# 03-POWER.net
KiCad netlist of a schematic drawn in Altium Designer
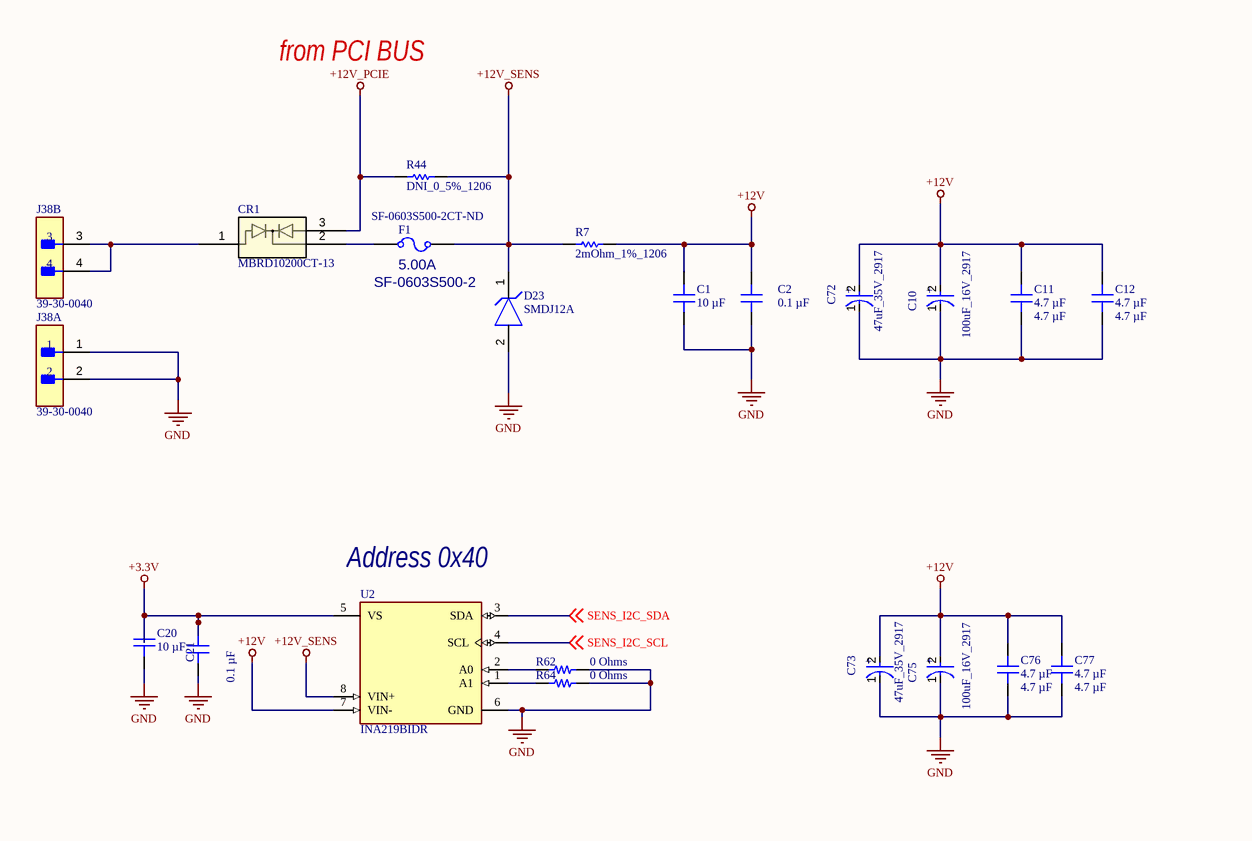
[diagram p0: 03-POWER.SchDoc, left]
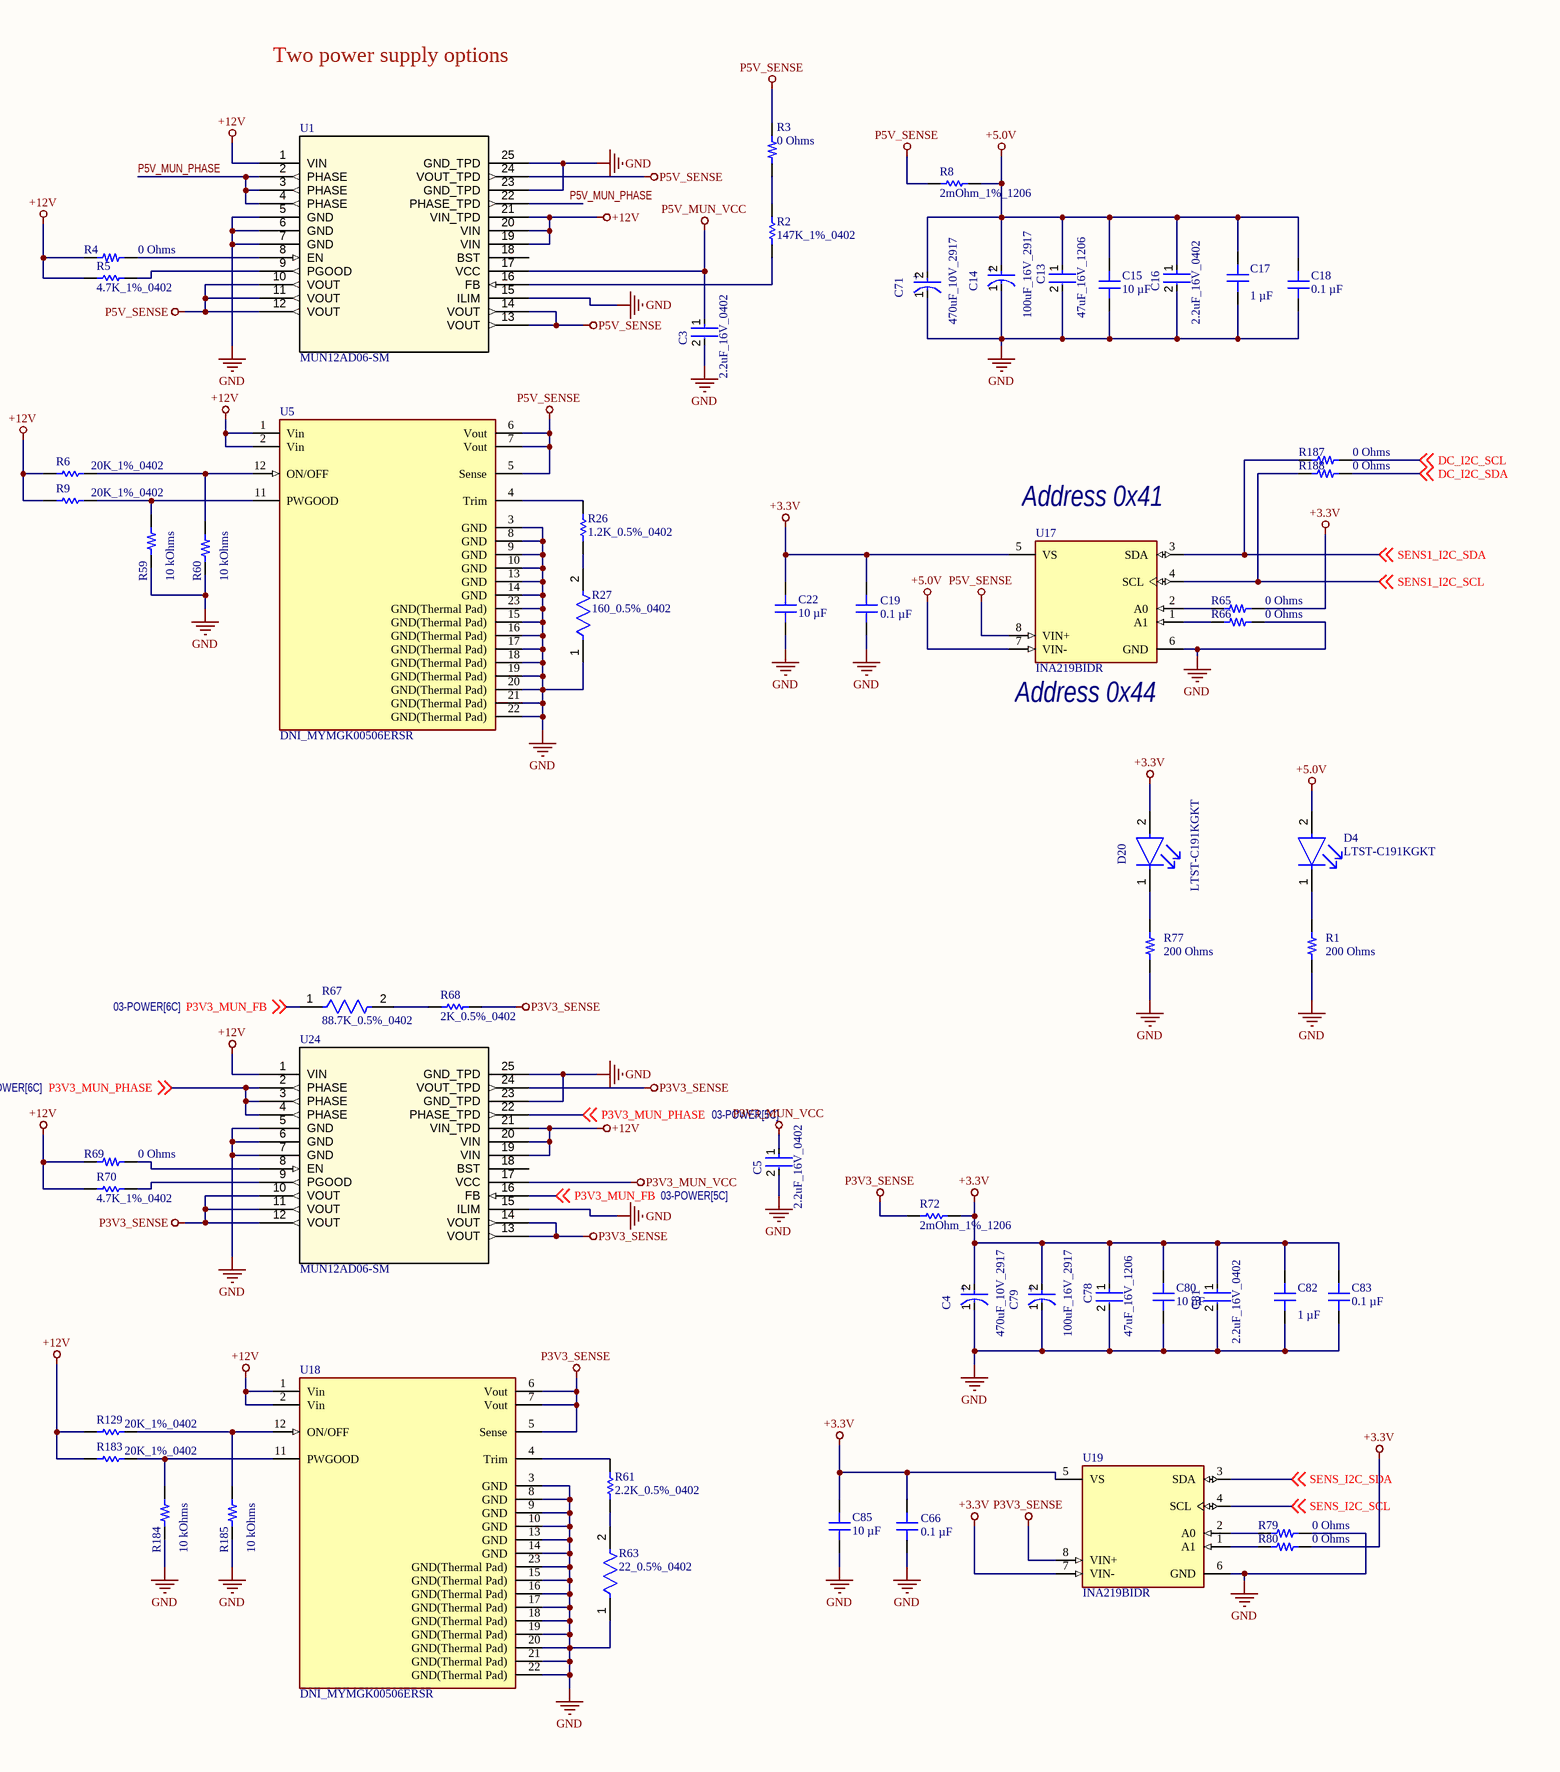
[diagram p1: 03-POWER.SchDoc, right]

(export (version "E")
  (design (tool "Eeschema 10.0.6"))
  (components
    (comp (ref "C1")
      (value "10 µF")
      (footprint "MURATA GRM21B 0805_2012")
      (description "CAP CER 10UF 25V X5R 0805")
      (fields
        (field (name "PART NUMBER") "GRM21BR61E106KA73L")
        (field (name "MANUFACTURER") "Murata Electronics")
      )
      (libsource (lib "Celestial Altium Library - altium_library") (part "Capacitor"))
    )
    (comp (ref "C2")
      (value "0.1 µF")
      (footprint "CAP 0402_1005")
      (description "CAP CER 0.1UF 50V X7R 0402")
      (fields (field (name "MANUFACTURER") "Yageo") (field (name "PART NUMBER") "CC0402KRX7R9BB104"))
      (libsource (lib "Celestial Altium Library - altium_library") (part "Capacitor"))
    )
    (comp (ref "C3")
      (value "2.2uF_16V_0402")
      (footprint "FP-C1005-050-0_05-IPC_A")
      (description "Multilayer Ceramic Capacitors 2.2μF ±10% 16V X5R SMD 0402")
      (fields (field (name "TOLERANCE") "10%"))
      (libsource (lib "Altium Content Vault") (part "b4654b650e69147ec39a6b967a45e02"))
    )
    (comp (ref "C4")
      (value "470uF_10V_2917")
      (footprint "FP-TAJE-MFG")
      (description "470uF 10V  ±10% 500mΩ 2917  SMD Tantalum Capacitor")
      (fields (field (name "TOLERANCE") "10%") (field (name "VOLTAGE") "10V"))
      (libsource (lib "Altium Content Vault") (part "203bc49f2ac43e59fd269a8c329ed05"))
    )
    (comp (ref "C5")
      (value "2.2uF_16V_0402")
      (footprint "FP-C1005-050-0_05-IPC_A")
      (description "Multilayer Ceramic Capacitors 2.2μF ±10% 16V X5R SMD 0402")
      (fields (field (name "TOLERANCE") "10%"))
      (libsource (lib "Altium Content Vault") (part "b4654b650e69147ec39a6b967a45e02"))
    )
    (comp (ref "C10")
      (value "100uF_16V_2917")
      (footprint "FP-T495D107K016ATE125-MFG")
      (description "CAP TANT 100UF 10% 16V 2917")
      (fields (field (name "VOLTAGE") "16V") (field (name "TOLERANCE") "10%"))
      (libsource (lib "Altium Content Vault") (part "a00bbbee19879c290e62620ae7e47b1"))
    )
    (comp (ref "C11")
      (value "4.7 µF")
      (footprint "MURATA CAP GRM31C 1206_3216")
      (description "CAP CER 4.7UF 50V X7R 1206")
      (fields
        (field (name "TOLERANCE") "±10%")
        (field (name "PART NUMBER") "GRM31CR71H475KA12L")
        (field (name "ALTIUM_VALUE") "4.7 µF")
      )
      (libsource (lib "Celestial Altium Library - altium_library") (part "Capacitor"))
    )
    (comp (ref "C12")
      (value "4.7 µF")
      (footprint "MURATA CAP GRM31C 1206_3216")
      (description "CAP CER 4.7UF 50V X7R 1206")
      (fields
        (field (name "TOLERANCE") "±10%")
        (field (name "PART NUMBER") "GRM31CR71H475KA12L")
        (field (name "ALTIUM_VALUE") "4.7 µF")
      )
      (libsource (lib "Celestial Altium Library - altium_library") (part "Capacitor"))
    )
    (comp (ref "C13")
      (value "47uF_16V_1206")
      (footprint "FP-C3216-160-0_2-MFG")
      (description "Multilayer Ceramic Capacitors 47uF ±20% 16V X5R SMD 1206")
      (fields (field (name "TOLERANCE") "20%"))
      (libsource (lib "Altium Content Vault") (part "11868f565c42a9108669ba33697ecf6"))
    )
    (comp (ref "C14")
      (value "100uF_16V_2917")
      (footprint "FP-T495D107K016ATE125-MFG")
      (description "CAP TANT 100UF 10% 16V 2917")
      (fields (field (name "VOLTAGE") "16V") (field (name "TOLERANCE") "10%"))
      (libsource (lib "Altium Content Vault") (part "a00bbbee19879c290e62620ae7e47b1"))
    )
    (comp (ref "C15")
      (value "10 µF")
      (footprint "MURATA GRM21B 0805_2012")
      (description "CAP CER 10UF 25V X5R 0805")
      (fields (field (name "TOLERANCE") "±10%") (field (name "PART NUMBER") "GRM21BR61E106KA73L"))
      (libsource (lib "Celestial Altium Library - altium_library") (part "Capacitor"))
    )
    (comp (ref "C16")
      (value "2.2uF_16V_0402")
      (footprint "FP-C1005-050-0_05-IPC_A")
      (description "Multilayer Ceramic Capacitors 2.2μF ±10% 16V X5R SMD 0402")
      (fields (field (name "TOLERANCE") "10%"))
      (libsource (lib "Altium Content Vault") (part "b4654b650e69147ec39a6b967a45e02"))
    )
    (comp (ref "C17")
      (value "1 µF")
      (footprint "CAP 0402_1005")
      (description "CAP CER 1UF 25V X5R 0402")
      (fields (field (name "TOLERANCE") "±10%") (field (name "PART NUMBER") "CC0402KRX5R8BB105"))
      (libsource (lib "Celestial Altium Library - altium_library") (part "Capacitor"))
    )
    (comp (ref "C18")
      (value "0.1 µF")
      (footprint "CAP 0402_1005")
      (description "CAP CER 0.1UF 50V X7R 0402")
      (fields (field (name "TOLERANCE") "±10%") (field (name "PART NUMBER") "CC0402KRX7R9BB104"))
      (libsource (lib "Celestial Altium Library - altium_library") (part "Capacitor"))
    )
    (comp (ref "C19")
      (value "0.1 µF")
      (footprint "CAP 0402_1005")
      (description "CAP CER 0.1UF 50V X7R 0402")
      (fields (field (name "PART NUMBER") "CC0402KRX7R9BB104") (field (name "MANUFACTURER") "Yageo"))
      (libsource (lib "Celestial Altium Library - altium_library") (part "Capacitor"))
    )
    (comp (ref "C20")
      (value "10 µF")
      (footprint "MURATA GRM21B 0805_2012")
      (description "CAP CER 10UF 25V X5R 0805")
      (fields (field (name "TOLERANCE") "±10%") (field (name "PART NUMBER") "GRM21BR61E106KA73L"))
      (libsource (lib "Celestial Altium Library - altium_library") (part "Capacitor"))
    )
    (comp (ref "C21")
      (value "0.1 µF")
      (footprint "CAP 0402_1005")
      (description "CAP CER 0.1UF 50V X7R 0402")
      (fields (field (name "PART NUMBER") "CC0402KRX7R9BB104") (field (name "MANUFACTURER") "Yageo"))
      (libsource (lib "Celestial Altium Library - altium_library") (part "Capacitor"))
    )
    (comp (ref "C22")
      (value "10 µF")
      (footprint "MURATA GRM21B 0805_2012")
      (description "CAP CER 10UF 25V X5R 0805")
      (fields (field (name "TOLERANCE") "±10%") (field (name "PART NUMBER") "GRM21BR61E106KA73L"))
      (libsource (lib "Celestial Altium Library - altium_library") (part "Capacitor"))
    )
    (comp (ref "C66")
      (value "0.1 µF")
      (footprint "CAP 0402_1005")
      (description "CAP CER 0.1UF 50V X7R 0402")
      (fields (field (name "PART NUMBER") "CC0402KRX7R9BB104") (field (name "MANUFACTURER") "Yageo"))
      (libsource (lib "Celestial Altium Library - altium_library") (part "Capacitor"))
    )
    (comp (ref "C71")
      (value "470uF_10V_2917")
      (footprint "FP-TAJE-MFG")
      (description "470uF 10V  ±10% 500mΩ 2917  SMD Tantalum Capacitor")
      (fields (field (name "TOLERANCE") "10%") (field (name "VOLTAGE") "10V"))
      (libsource (lib "Altium Content Vault") (part "203bc49f2ac43e59fd269a8c329ed05"))
    )
    (comp (ref "C72")
      (value "47uF_35V_2917")
      (footprint "FP-T521X476M035ATE030-MFG")
      (description "CAP TANT POLY 47UF 35V 2917")
      (fields (field (name "TOLERANCE") "20%"))
      (libsource (lib "Altium Content Vault") (part "a00bbbee19879c290e62620ae7e47b1"))
    )
    (comp (ref "C73")
      (value "47uF_35V_2917")
      (footprint "FP-T521X476M035ATE030-MFG")
      (description "CAP TANT POLY 47UF 35V 2917")
      (fields (field (name "TOLERANCE") "20%"))
      (libsource (lib "Altium Content Vault") (part "a00bbbee19879c290e62620ae7e47b1"))
    )
    (comp (ref "C75")
      (value "100uF_16V_2917")
      (footprint "FP-T495D107K016ATE125-MFG")
      (description "CAP TANT 100UF 10% 16V 2917")
      (fields (field (name "VOLTAGE") "16V") (field (name "TOLERANCE") "10%"))
      (libsource (lib "Altium Content Vault") (part "a00bbbee19879c290e62620ae7e47b1"))
    )
    (comp (ref "C76")
      (value "4.7 µF")
      (footprint "MURATA CAP GRM31C 1206_3216")
      (description "CAP CER 4.7UF 50V X7R 1206")
      (fields
        (field (name "TOLERANCE") "±10%")
        (field (name "PART NUMBER") "GRM31CR71H475KA12L")
        (field (name "ALTIUM_VALUE") "4.7 µF")
      )
      (libsource (lib "Celestial Altium Library - altium_library") (part "Capacitor"))
    )
    (comp (ref "C77")
      (value "4.7 µF")
      (footprint "MURATA CAP GRM31C 1206_3216")
      (description "CAP CER 4.7UF 50V X7R 1206")
      (fields
        (field (name "TOLERANCE") "±10%")
        (field (name "PART NUMBER") "GRM31CR71H475KA12L")
        (field (name "ALTIUM_VALUE") "4.7 µF")
      )
      (libsource (lib "Celestial Altium Library - altium_library") (part "Capacitor"))
    )
    (comp (ref "C78")
      (value "47uF_16V_1206")
      (footprint "FP-C3216-160-0_2-MFG")
      (description "Multilayer Ceramic Capacitors 47uF ±20% 16V X5R SMD 1206")
      (fields (field (name "TOLERANCE") "20%"))
      (libsource (lib "Altium Content Vault") (part "11868f565c42a9108669ba33697ecf6"))
    )
    (comp (ref "C79")
      (value "100uF_16V_2917")
      (footprint "FP-T495D107K016ATE125-MFG")
      (description "CAP TANT 100UF 10% 16V 2917")
      (fields (field (name "VOLTAGE") "16V") (field (name "TOLERANCE") "10%"))
      (libsource (lib "Altium Content Vault") (part "a00bbbee19879c290e62620ae7e47b1"))
    )
    (comp (ref "C80")
      (value "10 µF")
      (footprint "MURATA GRM21B 0805_2012")
      (description "CAP CER 10UF 25V X5R 0805")
      (fields (field (name "TOLERANCE") "±10%") (field (name "PART NUMBER") "GRM21BR61E106KA73L"))
      (libsource (lib "Celestial Altium Library - altium_library") (part "Capacitor"))
    )
    (comp (ref "C81")
      (value "2.2uF_16V_0402")
      (footprint "FP-C1005-050-0_05-IPC_A")
      (description "Multilayer Ceramic Capacitors 2.2μF ±10% 16V X5R SMD 0402")
      (fields (field (name "TOLERANCE") "10%"))
      (libsource (lib "Altium Content Vault") (part "b4654b650e69147ec39a6b967a45e02"))
    )
    (comp (ref "C82")
      (value "1 µF")
      (footprint "CAP 0402_1005")
      (description "CAP CER 1UF 25V X5R 0402")
      (fields (field (name "TOLERANCE") "±10%") (field (name "PART NUMBER") "CC0402KRX5R8BB105"))
      (libsource (lib "Celestial Altium Library - altium_library") (part "Capacitor"))
    )
    (comp (ref "C83")
      (value "0.1 µF")
      (footprint "CAP 0402_1005")
      (description "CAP CER 0.1UF 50V X7R 0402")
      (fields (field (name "TOLERANCE") "±10%") (field (name "PART NUMBER") "CC0402KRX7R9BB104"))
      (libsource (lib "Celestial Altium Library - altium_library") (part "Capacitor"))
    )
    (comp (ref "C85")
      (value "10 µF")
      (footprint "MURATA GRM21B 0805_2012")
      (description "CAP CER 10UF 25V X5R 0805")
      (fields (field (name "TOLERANCE") "±10%") (field (name "PART NUMBER") "GRM21BR61E106KA73L"))
      (libsource (lib "Celestial Altium Library - altium_library") (part "Capacitor"))
    )
    (comp (ref "CR1")
      (value "MBRD10200CT-13")
      (footprint "TO252(DPAK)_DIO")
      (description "No Description Available")
      (libsource (lib "MBRD10200CT-13") (part "MBRD10200CT-13"))
    )
    (comp (ref "D4")
      (value "LTST-C191KGKT")
      (footprint "FP-LTST-C191KGKT-MFG")
      (description "LED GREEN CLEAR SMD")
      (libsource (lib "Altium Content Vault") (part "8706943c75ba83719d021d2fdc84c58"))
    )
    (comp (ref "D20")
      (value "LTST-C191KGKT")
      (footprint "FP-LTST-C191KGKT-MFG")
      (description "LED GREEN CLEAR SMD")
      (libsource (lib "Altium Content Vault") (part "8706943c75ba83719d021d2fdc84c58"))
    )
    (comp (ref "D23")
      (value "SMDJ12A")
      (footprint "FP-DO-214AB_SMC_J-Bend-MFG")
      (description "TVS DIODE 12V 19.9V DO214AB")
      (libsource (lib "Altium Content Vault") (part "673ecd2ea4d7fb87b4005b0cb348b7d"))
    )
    (comp (ref "F1")
      (value "5.00A")
      (footprint "FUSM1608X60N")
      (description "FUSE SLOW 5.00A 32V M 0603")
      (fields
        (field (name "MFG PART NUM") "SF-0603S500-2")
        (field (name "VALENTIUM PART NUM") "<VALENTIUM>")
        (field (name "SUPPLIER PART NUMBER 1") "SF-0603S500-2CT-ND")
        (field (name "Comment") "FUSE_0603_5.00A")
      )
      (libsource (lib "Passives") (part "FUSE_0603_2.00A"))
    )
    (comp (ref "J38")
      (value "39-30-0040")
      (footprint "FP-39-30-0040-MFG")
      (description "CONN HEADER R/A 4POS 4.2MM")
      (fields
        (field (name "OCTOPART") "https://octopart.com/39-30-0040-molex-277428")
        (field (name "MANUFACTURER") "Molex")
      )
      (libsource (lib "Altium Content Vault") (part "ac72c5313ea981db199dbd0e8237b04"))
    )
    (comp (ref "R1")
      (value "200 Ohms")
      (footprint "YAGEO RES 0402_1005")
      (description "RES 200 OHM 1% 1/16W 0402")
      (fields (field (name "TOLERANCE") "±1%") (field (name "PART NUMBER") "RC0402FR-07200RL"))
      (libsource (lib "Celestial Altium Library - altium_library") (part "Resistor"))
    )
    (comp (ref "R2")
      (value "147K_1%_0402")
      (footprint "RESC1005X40X25ML05T10")
      (fields (field (name "MANUFACTURER") "Yageo / Phycomp") (field (name "PART NUMBER") "RC0402FR-07147KL"))
      (libsource (lib "Altium Content Vault") (part "RES"))
    )
    (comp (ref "R3")
      (value "0 Ohms")
      (footprint "YAGEO RES 0402_1005")
      (description "RES 0 OHM JUMPER 1/16W 0402")
      (fields (field (name "MANUFACTURER") "Yageo") (field (name "TOLERANCE") "Jumper"))
      (libsource (lib "Celestial Altium Library - altium_library") (part "Resistor"))
    )
    (comp (ref "R4")
      (value "0 Ohms")
      (footprint "YAGEO RES 0402_1005")
      (description "RES 0 OHM JUMPER 1/16W 0402")
      (fields (field (name "MANUFACTURER") "Yageo") (field (name "TOLERANCE") "Jumper"))
      (libsource (lib "Celestial Altium Library - altium_library") (part "Resistor"))
    )
    (comp (ref "R5")
      (value "4.7K_1%_0402")
      (footprint "RESC1005X40X25NL10T10")
      (fields (field (name "MANUFACTURER") "Bourns") (field (name "PART NUMBER") "CR0402-FX-4701GLF"))
      (libsource (lib "Altium Content Vault") (part "RES"))
    )
    (comp (ref "R6")
      (value "20K_1%_0402")
      (footprint "RESC1005X40X25NL10T10")
      (fields (field (name "PART NUMBER") "MC00625W0402120K") (field (name "MANUFACTURER") "Multicomp"))
      (libsource (lib "Altium Content Vault") (part "RES"))
    )
    (comp (ref "R7")
      (value "2mOhm_1%_1206")
      (footprint "RESC3216X89X64NL25T25")
      (fields (field (name "MANUFACTURER") "Vishay Dale") (field (name "PART NUMBER") "WSL12062L000FEA18"))
      (libsource (lib "Altium Content Vault") (part "RES"))
    )
    (comp (ref "R8")
      (value "2mOhm_1%_1206")
      (footprint "RESC3216X89X64NL25T25")
      (fields (field (name "MANUFACTURER") "Vishay Dale") (field (name "PART NUMBER") "WSL12062L000FEA18"))
      (libsource (lib "Altium Content Vault") (part "RES"))
    )
    (comp (ref "R9")
      (value "20K_1%_0402")
      (footprint "RESC1005X40X25NL10T10")
      (fields (field (name "PART NUMBER") "MC00625W0402120K") (field (name "MANUFACTURER") "Multicomp"))
      (libsource (lib "Altium Content Vault") (part "RES"))
    )
    (comp (ref "R26")
      (value "1.2K_0.5%_0402")
      (footprint "RESC1005X40X25ML10T10")
      (fields (field (name "PART NUMBER") "ERA-2AED122X") (field (name "MANUFACTURER") "Panasonic"))
      (libsource (lib "Altium Content Vault") (part "RES"))
    )
    (comp (ref "R27")
      (value "160_0.5%_0402")
      (footprint "FP-RT0402-MFG")
      (description "RES SMD 160 OHM 0.5% 1/16W 0402")
      (fields
        (field (name "TOLERANCE") "0.005")
        (field (name "OCTOPART") "https://octopart.com/rt0402dre07160rl-yageo-1216058")
      )
      (libsource (lib "Altium Content Vault") (part "1029c3af85768c4190bb7ad29bc67b5"))
    )
    (comp (ref "R44")
      (value "DNI_0_5%_1206")
      (footprint "RESC3116X65X50ML20T20")
      (fields (field (name "PART NUMBER") "CRCW12060000Z0EAHP") (field (name "MANUFACTURER") "Vishay Dale"))
      (libsource (lib "Altium Content Vault") (part "RES"))
    )
    (comp (ref "R59")
      (value "10 kOhms")
      (footprint "YAGEO RES 0402_1005")
      (description "RES 10K OHM 1% 1/16W 0402")
      (fields (field (name "MANUFACTURER") "Yageo") (field (name "PART NUMBER") "RC0402FR-0710KL"))
      (libsource (lib "Celestial Altium Library - altium_library") (part "Resistor"))
    )
    (comp (ref "R60")
      (value "10 kOhms")
      (footprint "YAGEO RES 0402_1005")
      (description "RES 10K OHM 1% 1/16W 0402")
      (fields (field (name "MANUFACTURER") "Yageo") (field (name "PART NUMBER") "RC0402FR-0710KL"))
      (libsource (lib "Celestial Altium Library - altium_library") (part "Resistor"))
    )
    (comp (ref "R61")
      (value "2.2K_0.5%_0402")
      (footprint "RESC1005X40X25ML10T10")
      (fields (field (name "PART NUMBER") "ERA-2AED222X") (field (name "MANUFACTURER") "Panasonic"))
      (libsource (lib "Altium Content Vault") (part "RES"))
    )
    (comp (ref "R62")
      (value "0 Ohms")
      (footprint "YAGEO RES 0402_1005")
      (description "RES 0 OHM JUMPER 1/16W 0402")
      (fields (field (name "MANUFACTURER") "Yageo") (field (name "TOLERANCE") "Jumper"))
      (libsource (lib "Celestial Altium Library - altium_library") (part "Resistor"))
    )
    (comp (ref "R63")
      (value "22_0.5%_0402")
      (footprint "FP-RG1005-IPC_A")
      (description "Automotive Metal Thin Film Chip Resistor, 0402, 22Ω, 0.5%, 100ppm/°C, 0.0625W, 75V")
      (fields (field (name "TOLERANCE") "0.5%"))
      (libsource (lib "Altium Content Vault") (part "1029c3af85768c4190bb7ad29bc67b5"))
    )
    (comp (ref "R64")
      (value "0 Ohms")
      (footprint "YAGEO RES 0402_1005")
      (description "RES 0 OHM JUMPER 1/16W 0402")
      (fields (field (name "MANUFACTURER") "Yageo") (field (name "TOLERANCE") "Jumper"))
      (libsource (lib "Celestial Altium Library - altium_library") (part "Resistor"))
    )
    (comp (ref "R65")
      (value "0 Ohms")
      (footprint "YAGEO RES 0402_1005")
      (description "RES 0 OHM JUMPER 1/16W 0402")
      (fields (field (name "MANUFACTURER") "Yageo") (field (name "TOLERANCE") "Jumper"))
      (libsource (lib "Celestial Altium Library - altium_library") (part "Resistor"))
    )
    (comp (ref "R66")
      (value "0 Ohms")
      (footprint "YAGEO RES 0402_1005")
      (description "RES 0 OHM JUMPER 1/16W 0402")
      (fields (field (name "MANUFACTURER") "Yageo") (field (name "TOLERANCE") "Jumper"))
      (libsource (lib "Celestial Altium Library - altium_library") (part "Resistor"))
    )
    (comp (ref "R67")
      (value "88.7K_0.5%_0402")
      (footprint "FP-RT0402-MFG")
      (description "RES SMD 88.7K OHM 0.5% 1/16W")
      (fields
        (field (name "OCTOPART") "https://octopart.com/rt0402dre0788k7l-yageo-1439224")
        (field (name "MANUFACTURER") "Yageo")
      )
      (libsource (lib "Altium Content Vault") (part "1029c3af85768c4190bb7ad29bc67b5"))
    )
    (comp (ref "R68")
      (value "2K_0.5%_0402")
      (footprint "RESC1005X35X25LL10T10")
      (fields (field (name "PART NUMBER") "RT0402DRD072KL") (field (name "MANUFACTURER") "Yageo"))
      (libsource (lib "Altium Content Vault") (part "RES"))
    )
    (comp (ref "R69")
      (value "0 Ohms")
      (footprint "YAGEO RES 0402_1005")
      (description "RES 0 OHM JUMPER 1/16W 0402")
      (fields (field (name "MANUFACTURER") "Yageo") (field (name "TOLERANCE") "Jumper"))
      (libsource (lib "Celestial Altium Library - altium_library") (part "Resistor"))
    )
    (comp (ref "R70")
      (value "4.7K_1%_0402")
      (footprint "RESC1005X40X25NL10T10")
      (fields (field (name "MANUFACTURER") "Bourns") (field (name "PART NUMBER") "CR0402-FX-4701GLF"))
      (libsource (lib "Altium Content Vault") (part "RES"))
    )
    (comp (ref "R72")
      (value "2mOhm_1%_1206")
      (footprint "RESC3216X89X64NL25T25")
      (fields (field (name "MANUFACTURER") "Vishay Dale") (field (name "PART NUMBER") "WSL12062L000FEA18"))
      (libsource (lib "Altium Content Vault") (part "RES"))
    )
    (comp (ref "R77")
      (value "200 Ohms")
      (footprint "YAGEO RES 0402_1005")
      (description "RES 200 OHM 1% 1/16W 0402")
      (fields (field (name "TOLERANCE") "±1%") (field (name "PART NUMBER") "RC0402FR-07200RL"))
      (libsource (lib "Celestial Altium Library - altium_library") (part "Resistor"))
    )
    (comp (ref "R79")
      (value "0 Ohms")
      (footprint "YAGEO RES 0402_1005")
      (description "RES 0 OHM JUMPER 1/16W 0402")
      (fields (field (name "MANUFACTURER") "Yageo") (field (name "TOLERANCE") "Jumper"))
      (libsource (lib "Celestial Altium Library - altium_library") (part "Resistor"))
    )
    (comp (ref "R80")
      (value "0 Ohms")
      (footprint "YAGEO RES 0402_1005")
      (description "RES 0 OHM JUMPER 1/16W 0402")
      (fields (field (name "MANUFACTURER") "Yageo") (field (name "TOLERANCE") "Jumper"))
      (libsource (lib "Celestial Altium Library - altium_library") (part "Resistor"))
    )
    (comp (ref "R129")
      (value "20K_1%_0402")
      (footprint "RESC1005X40X25NL10T10")
      (fields (field (name "PART NUMBER") "MC00625W0402120K") (field (name "MANUFACTURER") "Multicomp"))
      (libsource (lib "Altium Content Vault") (part "RES"))
    )
    (comp (ref "R183")
      (value "20K_1%_0402")
      (footprint "RESC1005X40X25NL10T10")
      (fields (field (name "PART NUMBER") "MC00625W0402120K") (field (name "MANUFACTURER") "Multicomp"))
      (libsource (lib "Altium Content Vault") (part "RES"))
    )
    (comp (ref "R184")
      (value "10 kOhms")
      (footprint "YAGEO RES 0402_1005")
      (description "RES 10K OHM 1% 1/16W 0402")
      (fields (field (name "MANUFACTURER") "Yageo") (field (name "PART NUMBER") "RC0402FR-0710KL"))
      (libsource (lib "Celestial Altium Library - altium_library") (part "Resistor"))
    )
    (comp (ref "R185")
      (value "10 kOhms")
      (footprint "YAGEO RES 0402_1005")
      (description "RES 10K OHM 1% 1/16W 0402")
      (fields (field (name "MANUFACTURER") "Yageo") (field (name "PART NUMBER") "RC0402FR-0710KL"))
      (libsource (lib "Celestial Altium Library - altium_library") (part "Resistor"))
    )
    (comp (ref "R187")
      (value "0 Ohms")
      (footprint "YAGEO RES 0402_1005")
      (description "RES 0 OHM JUMPER 1/16W 0402")
      (fields (field (name "MANUFACTURER") "Yageo") (field (name "TOLERANCE") "Jumper"))
      (libsource (lib "Celestial Altium Library - altium_library") (part "Resistor"))
    )
    (comp (ref "R188")
      (value "0 Ohms")
      (footprint "YAGEO RES 0402_1005")
      (description "RES 0 OHM JUMPER 1/16W 0402")
      (fields (field (name "MANUFACTURER") "Yageo") (field (name "TOLERANCE") "Jumper"))
      (libsource (lib "Celestial Altium Library - altium_library") (part "Resistor"))
    )
    (comp (ref "U1")
      (value "MUN12AD06-SM")
      (footprint "MUN12AD06-SM_CYN")
      (description "No Description Available")
      (libsource (lib "MUN12AD06-SM") (part "MUN12AD06-SM"))
    )
    (comp (ref "U2")
      (value "INA219BIDR")
      (footprint "FP-D0008A-MFG")
      (description "IC MONITOR PWR/CURR BIDIR 8-SOIC")
      (libsource (lib "Altium Content Vault") (part "41cc1aee4cbc9fa2660a15773fa0e79"))
    )
    (comp (ref "U5")
      (value "DNI_MYMGK00506ERSR")
      (footprint "FP-MYMGK-12-MFG")
      (description "DC DC CONVERTER 0.7-5V")
      (libsource (lib "Altium Content Vault") (part "57b8017c1ce60d7b1362a625e7a4ba1"))
    )
    (comp (ref "U17")
      (value "INA219BIDR")
      (footprint "FP-D0008A-MFG")
      (description "IC MONITOR PWR/CURR BIDIR 8-SOIC")
      (libsource (lib "Altium Content Vault") (part "41cc1aee4cbc9fa2660a15773fa0e79"))
    )
    (comp (ref "U18")
      (value "DNI_MYMGK00506ERSR")
      (footprint "FP-MYMGK-12-MFG")
      (description "DC DC CONVERTER 0.7-5V")
      (libsource (lib "Altium Content Vault") (part "57b8017c1ce60d7b1362a625e7a4ba1"))
    )
    (comp (ref "U19")
      (value "INA219BIDR")
      (footprint "FP-D0008A-MFG")
      (description "IC MONITOR PWR/CURR BIDIR 8-SOIC")
      (libsource (lib "Altium Content Vault") (part "41cc1aee4cbc9fa2660a15773fa0e79"))
    )
    (comp (ref "U24")
      (value "MUN12AD06-SM")
      (footprint "MUN12AD06-SM_CYN")
      (description "No Description Available")
      (libsource (lib "MUN12AD06-SM") (part "MUN12AD06-SM"))
    )
  )
  (nets
    (net (code "1") (name "+3.3V") (class "Default")
      (node (ref "C19") (pin "2") (pinfunction "2_2") (pintype "passive"))
      (node (ref "C20") (pin "2") (pinfunction "2_2") (pintype "passive"))
      (node (ref "C21") (pin "2") (pinfunction "2_2") (pintype "passive"))
      (node (ref "C22") (pin "2") (pinfunction "2_2") (pintype "passive"))
      (node (ref "C4") (pin "2") (pinfunction "A_2") (pintype "passive"))
      (node (ref "C66") (pin "2") (pinfunction "2_2") (pintype "passive"))
      (node (ref "C78") (pin "1") (pinfunction "1_1") (pintype "passive"))
      (node (ref "C79") (pin "2") (pinfunction "A_2") (pintype "passive"))
      (node (ref "C80") (pin "2") (pinfunction "2_2") (pintype "passive"))
      (node (ref "C81") (pin "1") (pinfunction "1_1") (pintype "passive"))
      (node (ref "C82") (pin "2") (pinfunction "2_2") (pintype "passive"))
      (node (ref "C83") (pin "1") (pinfunction "1_1") (pintype "passive"))
      (node (ref "C85") (pin "2") (pinfunction "2_2") (pintype "passive"))
      (node (ref "D20") (pin "2") (pinfunction "A_2") (pintype "passive"))
      (node (ref "R65") (pin "2") (pinfunction "2_2") (pintype "passive"))
      (node (ref "R72") (pin "2") (pinfunction "2_2") (pintype "passive"))
      (node (ref "R80") (pin "2") (pinfunction "2_2") (pintype "passive"))
      (node (ref "U17") (pin "5") (pinfunction "VS_5") (pintype "power_in"))
      (node (ref "U19") (pin "5") (pinfunction "VS_5") (pintype "power_in"))
      (node (ref "U19") (pin "7") (pinfunction "VIN-_7") (pintype "input"))
      (node (ref "U2") (pin "5") (pinfunction "VS_5") (pintype "power_in"))
    )
    (net (code "2") (name "+5.0V") (class "Default")
      (node (ref "C13") (pin "1") (pinfunction "1_1") (pintype "passive"))
      (node (ref "C14") (pin "2") (pinfunction "A_2") (pintype "passive"))
      (node (ref "C15") (pin "2") (pinfunction "2_2") (pintype "passive"))
      (node (ref "C16") (pin "1") (pinfunction "1_1") (pintype "passive"))
      (node (ref "C17") (pin "2") (pinfunction "2_2") (pintype "passive"))
      (node (ref "C18") (pin "1") (pinfunction "1_1") (pintype "passive"))
      (node (ref "C71") (pin "2") (pinfunction "A_2") (pintype "passive"))
      (node (ref "D4") (pin "2") (pinfunction "A_2") (pintype "passive"))
      (node (ref "R8") (pin "2") (pinfunction "2_2") (pintype "passive"))
      (node (ref "U17") (pin "7") (pinfunction "VIN-_7") (pintype "input"))
    )
    (net (code "3") (name "+12V") (class "Default")
      (node (ref "C1") (pin "1") (pinfunction "1_1") (pintype "passive"))
      (node (ref "C10") (pin "2") (pinfunction "A_2") (pintype "passive"))
      (node (ref "C11") (pin "2") (pinfunction "2_2") (pintype "passive"))
      (node (ref "C12") (pin "2") (pinfunction "2_2") (pintype "passive"))
      (node (ref "C2") (pin "2") (pinfunction "2_2") (pintype "passive"))
      (node (ref "C72") (pin "2") (pinfunction "A_2") (pintype "passive"))
      (node (ref "C73") (pin "2") (pinfunction "A_2") (pintype "passive"))
      (node (ref "C75") (pin "2") (pinfunction "A_2") (pintype "passive"))
      (node (ref "C76") (pin "2") (pinfunction "2_2") (pintype "passive"))
      (node (ref "C77") (pin "2") (pinfunction "2_2") (pintype "passive"))
      (node (ref "R129") (pin "1") (pinfunction "1_1") (pintype "passive"))
      (node (ref "R183") (pin "1") (pinfunction "1_1") (pintype "passive"))
      (node (ref "R4") (pin "1") (pinfunction "1_1") (pintype "passive"))
      (node (ref "R5") (pin "2") (pinfunction "2_2") (pintype "passive"))
      (node (ref "R6") (pin "1") (pinfunction "1_1") (pintype "passive"))
      (node (ref "R69") (pin "1") (pinfunction "1_1") (pintype "passive"))
      (node (ref "R7") (pin "2") (pinfunction "2_2") (pintype "passive"))
      (node (ref "R70") (pin "2") (pinfunction "2_2") (pintype "passive"))
      (node (ref "R9") (pin "1") (pinfunction "1_1") (pintype "passive"))
      (node (ref "U1") (pin "1") (pinfunction "VIN_1") (pintype "power_in"))
      (node (ref "U1") (pin "19") (pinfunction "VIN_19") (pintype "power_in"))
      (node (ref "U1") (pin "20") (pinfunction "VIN_20") (pintype "power_in"))
      (node (ref "U1") (pin "21") (pinfunction "VIN_TPD_21") (pintype "power_in"))
      (node (ref "U18") (pin "1") (pinfunction "Vin_1") (pintype "power_in"))
      (node (ref "U18") (pin "2") (pinfunction "Vin_2") (pintype "power_in"))
      (node (ref "U2") (pin "7") (pinfunction "VIN-_7") (pintype "input"))
      (node (ref "U24") (pin "1") (pinfunction "VIN_1") (pintype "power_in"))
      (node (ref "U24") (pin "19") (pinfunction "VIN_19") (pintype "power_in"))
      (node (ref "U24") (pin "20") (pinfunction "VIN_20") (pintype "power_in"))
      (node (ref "U24") (pin "21") (pinfunction "VIN_TPD_21") (pintype "power_in"))
      (node (ref "U5") (pin "1") (pinfunction "Vin_1") (pintype "power_in"))
      (node (ref "U5") (pin "2") (pinfunction "Vin_2") (pintype "power_in"))
    )
    (net (code "4") (name "+12V_PCIE") (class "Default")
      (node (ref "CR1") (pin "3") (pinfunction "3_3") (pintype "passive"))
      (node (ref "R44") (pin "1") (pinfunction "1_1") (pintype "passive"))
    )
    (net (code "5") (name "+12V_SENS") (class "Default")
      (node (ref "D23") (pin "1") (pinfunction "C_1") (pintype "passive"))
      (node (ref "F1") (pin "2") (pinfunction "2_2") (pintype "passive"))
      (node (ref "R44") (pin "2") (pinfunction "2_2") (pintype "passive"))
      (node (ref "R7") (pin "1") (pinfunction "1_1") (pintype "passive"))
      (node (ref "U2") (pin "8") (pinfunction "VIN+_8") (pintype "input"))
    )
    (net (code "6") (name "/P5V_MUN_PHASE") (class "Default")
      (node (ref "U1") (pin "2") (pinfunction "PHASE_2") (pintype "output"))
      (node (ref "U1") (pin "22") (pinfunction "PHASE_TPD_22") (pintype "output"))
      (node (ref "U1") (pin "3") (pinfunction "PHASE_3") (pintype "output"))
      (node (ref "U1") (pin "4") (pinfunction "PHASE_4") (pintype "output"))
    )
    (net (code "7") (name "DC_I2C_SCL") (class "Default")
      (node (ref "R187") (pin "2") (pinfunction "2_2") (pintype "passive"))
    )
    (net (code "8") (name "DC_I2C_SDA") (class "Default")
      (node (ref "R188") (pin "2") (pinfunction "2_2") (pintype "passive"))
    )
    (net (code "9") (name "GND") (class "Default")
      (node (ref "C1") (pin "2") (pinfunction "2_2") (pintype "passive"))
      (node (ref "C10") (pin "1") (pinfunction "C_1") (pintype "passive"))
      (node (ref "C11") (pin "1") (pinfunction "1_1") (pintype "passive"))
      (node (ref "C12") (pin "1") (pinfunction "1_1") (pintype "passive"))
      (node (ref "C13") (pin "2") (pinfunction "2_2") (pintype "passive"))
      (node (ref "C14") (pin "1") (pinfunction "C_1") (pintype "passive"))
      (node (ref "C15") (pin "1") (pinfunction "1_1") (pintype "passive"))
      (node (ref "C16") (pin "2") (pinfunction "2_2") (pintype "passive"))
      (node (ref "C17") (pin "1") (pinfunction "1_1") (pintype "passive"))
      (node (ref "C18") (pin "2") (pinfunction "2_2") (pintype "passive"))
      (node (ref "C19") (pin "1") (pinfunction "1_1") (pintype "passive"))
      (node (ref "C2") (pin "1") (pinfunction "1_1") (pintype "passive"))
      (node (ref "C20") (pin "1") (pinfunction "1_1") (pintype "passive"))
      (node (ref "C21") (pin "1") (pinfunction "1_1") (pintype "passive"))
      (node (ref "C22") (pin "1") (pinfunction "1_1") (pintype "passive"))
      (node (ref "C3") (pin "2") (pinfunction "2_2") (pintype "passive"))
      (node (ref "C4") (pin "1") (pinfunction "C_1") (pintype "passive"))
      (node (ref "C5") (pin "2") (pinfunction "2_2") (pintype "passive"))
      (node (ref "C66") (pin "1") (pinfunction "1_1") (pintype "passive"))
      (node (ref "C71") (pin "1") (pinfunction "C_1") (pintype "passive"))
      (node (ref "C72") (pin "1") (pinfunction "C_1") (pintype "passive"))
      (node (ref "C73") (pin "1") (pinfunction "C_1") (pintype "passive"))
      (node (ref "C75") (pin "1") (pinfunction "C_1") (pintype "passive"))
      (node (ref "C76") (pin "1") (pinfunction "1_1") (pintype "passive"))
      (node (ref "C77") (pin "1") (pinfunction "1_1") (pintype "passive"))
      (node (ref "C78") (pin "2") (pinfunction "2_2") (pintype "passive"))
      (node (ref "C79") (pin "1") (pinfunction "C_1") (pintype "passive"))
      (node (ref "C80") (pin "1") (pinfunction "1_1") (pintype "passive"))
      (node (ref "C81") (pin "2") (pinfunction "2_2") (pintype "passive"))
      (node (ref "C82") (pin "1") (pinfunction "1_1") (pintype "passive"))
      (node (ref "C83") (pin "2") (pinfunction "2_2") (pintype "passive"))
      (node (ref "C85") (pin "1") (pinfunction "1_1") (pintype "passive"))
      (node (ref "D23") (pin "2") (pinfunction "A_2") (pintype "passive"))
      (node (ref "J38") (pin "1") (pinfunction "1_1") (pintype "passive"))
      (node (ref "J38") (pin "2") (pinfunction "2_2") (pintype "passive"))
      (node (ref "R1") (pin "1") (pinfunction "1_1") (pintype "passive"))
      (node (ref "R184") (pin "1") (pinfunction "1_1") (pintype "passive"))
      (node (ref "R185") (pin "1") (pinfunction "1_1") (pintype "passive"))
      (node (ref "R27") (pin "1") (pinfunction "1_1") (pintype "passive"))
      (node (ref "R59") (pin "1") (pinfunction "1_1") (pintype "passive"))
      (node (ref "R60") (pin "1") (pinfunction "1_1") (pintype "passive"))
      (node (ref "R62") (pin "2") (pinfunction "2_2") (pintype "passive"))
      (node (ref "R63") (pin "1") (pinfunction "1_1") (pintype "passive"))
      (node (ref "R64") (pin "2") (pinfunction "2_2") (pintype "passive"))
      (node (ref "R66") (pin "2") (pinfunction "2_2") (pintype "passive"))
      (node (ref "R77") (pin "1") (pinfunction "1_1") (pintype "passive"))
      (node (ref "R79") (pin "2") (pinfunction "2_2") (pintype "passive"))
      (node (ref "U1") (pin "15") (pinfunction "ILIM_15") (pintype "passive"))
      (node (ref "U1") (pin "23") (pinfunction "GND_TPD_23") (pintype "power_in"))
      (node (ref "U1") (pin "25") (pinfunction "GND_TPD_25") (pintype "power_in"))
      (node (ref "U1") (pin "5") (pinfunction "GND_5") (pintype "power_in"))
      (node (ref "U1") (pin "6") (pinfunction "GND_6") (pintype "power_in"))
      (node (ref "U1") (pin "7") (pinfunction "GND_7") (pintype "power_in"))
      (node (ref "U17") (pin "6") (pinfunction "GND_6") (pintype "power_in"))
      (node (ref "U18") (pin "10") (pinfunction "GND_10") (pintype "power_in"))
      (node (ref "U18") (pin "13") (pinfunction "GND_13") (pintype "power_in"))
      (node (ref "U18") (pin "14") (pinfunction "GND_14") (pintype "power_in"))
      (node (ref "U18") (pin "15") (pinfunction "GND(Thermal_Pad)_15") (pintype "power_in"))
      (node (ref "U18") (pin "16") (pinfunction "GND(Thermal_Pad)_16") (pintype "power_in"))
      (node (ref "U18") (pin "17") (pinfunction "GND(Thermal_Pad)_17") (pintype "power_in"))
      (node (ref "U18") (pin "18") (pinfunction "GND(Thermal_Pad)_18") (pintype "power_in"))
      (node (ref "U18") (pin "19") (pinfunction "GND(Thermal_Pad)_19") (pintype "power_in"))
      (node (ref "U18") (pin "20") (pinfunction "GND(Thermal_Pad)_20") (pintype "power_in"))
      (node (ref "U18") (pin "21") (pinfunction "GND(Thermal_Pad)_21") (pintype "power_in"))
      (node (ref "U18") (pin "22") (pinfunction "GND(Thermal_Pad)_22") (pintype "power_in"))
      (node (ref "U18") (pin "23") (pinfunction "GND(Thermal_Pad)_23") (pintype "power_in"))
      (node (ref "U18") (pin "3") (pinfunction "GND_3") (pintype "power_in"))
      (node (ref "U18") (pin "8") (pinfunction "GND_8") (pintype "power_in"))
      (node (ref "U18") (pin "9") (pinfunction "GND_9") (pintype "power_in"))
      (node (ref "U19") (pin "6") (pinfunction "GND_6") (pintype "power_in"))
      (node (ref "U2") (pin "6") (pinfunction "GND_6") (pintype "power_in"))
      (node (ref "U24") (pin "15") (pinfunction "ILIM_15") (pintype "passive"))
      (node (ref "U24") (pin "23") (pinfunction "GND_TPD_23") (pintype "power_in"))
      (node (ref "U24") (pin "25") (pinfunction "GND_TPD_25") (pintype "power_in"))
      (node (ref "U24") (pin "5") (pinfunction "GND_5") (pintype "power_in"))
      (node (ref "U24") (pin "6") (pinfunction "GND_6") (pintype "power_in"))
      (node (ref "U24") (pin "7") (pinfunction "GND_7") (pintype "power_in"))
      (node (ref "U5") (pin "10") (pinfunction "GND_10") (pintype "power_in"))
      (node (ref "U5") (pin "13") (pinfunction "GND_13") (pintype "power_in"))
      (node (ref "U5") (pin "14") (pinfunction "GND_14") (pintype "power_in"))
      (node (ref "U5") (pin "15") (pinfunction "GND(Thermal_Pad)_15") (pintype "power_in"))
      (node (ref "U5") (pin "16") (pinfunction "GND(Thermal_Pad)_16") (pintype "power_in"))
      (node (ref "U5") (pin "17") (pinfunction "GND(Thermal_Pad)_17") (pintype "power_in"))
      (node (ref "U5") (pin "18") (pinfunction "GND(Thermal_Pad)_18") (pintype "power_in"))
      (node (ref "U5") (pin "19") (pinfunction "GND(Thermal_Pad)_19") (pintype "power_in"))
      (node (ref "U5") (pin "20") (pinfunction "GND(Thermal_Pad)_20") (pintype "power_in"))
      (node (ref "U5") (pin "21") (pinfunction "GND(Thermal_Pad)_21") (pintype "power_in"))
      (node (ref "U5") (pin "22") (pinfunction "GND(Thermal_Pad)_22") (pintype "power_in"))
      (node (ref "U5") (pin "23") (pinfunction "GND(Thermal_Pad)_23") (pintype "power_in"))
      (node (ref "U5") (pin "3") (pinfunction "GND_3") (pintype "power_in"))
      (node (ref "U5") (pin "8") (pinfunction "GND_8") (pintype "power_in"))
      (node (ref "U5") (pin "9") (pinfunction "GND_9") (pintype "power_in"))
    )
    (net (code "10") (name "Net-(CR1-Pad1)") (class "Default")
      (node (ref "CR1") (pin "1") (pinfunction "1_1") (pintype "passive"))
      (node (ref "J38") (pin "3") (pinfunction "3_3") (pintype "passive"))
      (node (ref "J38") (pin "4") (pinfunction "4_4") (pintype "passive"))
    )
    (net (code "11") (name "Net-(CR1-Pad2)") (class "Default")
      (node (ref "CR1") (pin "2") (pinfunction "2_2") (pintype "passive"))
      (node (ref "F1") (pin "1") (pinfunction "1_1") (pintype "passive"))
    )
    (net (code "12") (name "Net-(D4-C)") (class "Default")
      (node (ref "D4") (pin "1") (pinfunction "C_1") (pintype "passive"))
      (node (ref "R1") (pin "2") (pinfunction "2_2") (pintype "passive"))
    )
    (net (code "13") (name "Net-(D20-C)") (class "Default")
      (node (ref "D20") (pin "1") (pinfunction "C_1") (pintype "passive"))
      (node (ref "R77") (pin "2") (pinfunction "2_2") (pintype "passive"))
    )
    (net (code "14") (name "Net-(R2-Pad2)") (class "Default")
      (node (ref "R2") (pin "2") (pinfunction "2_2") (pintype "passive"))
      (node (ref "R3") (pin "1") (pinfunction "1_1") (pintype "passive"))
    )
    (net (code "15") (name "Net-(R26-Pad1)") (class "Default")
      (node (ref "R26") (pin "1") (pinfunction "1_1") (pintype "passive"))
      (node (ref "R27") (pin "2") (pinfunction "2_2") (pintype "passive"))
    )
    (net (code "16") (name "Net-(R61-Pad1)") (class "Default")
      (node (ref "R61") (pin "1") (pinfunction "1_1") (pintype "passive"))
      (node (ref "R63") (pin "2") (pinfunction "2_2") (pintype "passive"))
    )
    (net (code "17") (name "Net-(R67-Pad2)") (class "Default")
      (node (ref "R67") (pin "2") (pinfunction "2_2") (pintype "passive"))
      (node (ref "R68") (pin "1") (pinfunction "1_1") (pintype "passive"))
    )
    (net (code "18") (name "Net-(U1-EN)") (class "Default")
      (node (ref "R4") (pin "2") (pinfunction "2_2") (pintype "passive"))
      (node (ref "U1") (pin "8") (pinfunction "EN_8") (pintype "input"))
    )
    (net (code "19") (name "Net-(U1-FB)") (class "Default")
      (node (ref "R2") (pin "1") (pinfunction "1_1") (pintype "passive"))
      (node (ref "U1") (pin "16") (pinfunction "FB_16") (pintype "input"))
    )
    (net (code "20") (name "Net-(U1-PGOOD)") (class "Default")
      (node (ref "R5") (pin "1") (pinfunction "1_1") (pintype "passive"))
      (node (ref "U1") (pin "9") (pinfunction "PGOOD_9") (pintype "output"))
    )
    (net (code "21") (name "Net-(U2-A0)") (class "Default")
      (node (ref "R62") (pin "1") (pinfunction "1_1") (pintype "passive"))
      (node (ref "U2") (pin "2") (pinfunction "A0_2") (pintype "input"))
    )
    (net (code "22") (name "Net-(U2-A1)") (class "Default")
      (node (ref "R64") (pin "1") (pinfunction "1_1") (pintype "passive"))
      (node (ref "U2") (pin "1") (pinfunction "A1_1") (pintype "input"))
    )
    (net (code "23") (name "Net-(U5-ON{slash}OFF)") (class "Default")
      (node (ref "R6") (pin "2") (pinfunction "2_2") (pintype "passive"))
      (node (ref "R60") (pin "2") (pinfunction "2_2") (pintype "passive"))
      (node (ref "U5") (pin "12") (pinfunction "ON/OFF_12") (pintype "input"))
    )
    (net (code "24") (name "Net-(U5-PWGOOD)") (class "Default")
      (node (ref "R59") (pin "2") (pinfunction "2_2") (pintype "passive"))
      (node (ref "R9") (pin "2") (pinfunction "2_2") (pintype "passive"))
      (node (ref "U5") (pin "11") (pinfunction "PWGOOD_11") (pintype "open_collector"))
    )
    (net (code "25") (name "Net-(U5-Trim)") (class "Default")
      (node (ref "R26") (pin "2") (pinfunction "2_2") (pintype "passive"))
      (node (ref "U5") (pin "4") (pinfunction "Trim_4") (pintype "passive"))
    )
    (net (code "26") (name "Net-(U17-A0)") (class "Default")
      (node (ref "R65") (pin "1") (pinfunction "1_1") (pintype "passive"))
      (node (ref "U17") (pin "2") (pinfunction "A0_2") (pintype "input"))
    )
    (net (code "27") (name "Net-(U17-A1)") (class "Default")
      (node (ref "R66") (pin "1") (pinfunction "1_1") (pintype "passive"))
      (node (ref "U17") (pin "1") (pinfunction "A1_1") (pintype "input"))
    )
    (net (code "28") (name "Net-(U18-ON{slash}OFF)") (class "Default")
      (node (ref "R129") (pin "2") (pinfunction "2_2") (pintype "passive"))
      (node (ref "R185") (pin "2") (pinfunction "2_2") (pintype "passive"))
      (node (ref "U18") (pin "12") (pinfunction "ON/OFF_12") (pintype "input"))
    )
    (net (code "29") (name "Net-(U18-PWGOOD)") (class "Default")
      (node (ref "R183") (pin "2") (pinfunction "2_2") (pintype "passive"))
      (node (ref "R184") (pin "2") (pinfunction "2_2") (pintype "passive"))
      (node (ref "U18") (pin "11") (pinfunction "PWGOOD_11") (pintype "open_collector"))
    )
    (net (code "30") (name "Net-(U18-Trim)") (class "Default")
      (node (ref "R61") (pin "2") (pinfunction "2_2") (pintype "passive"))
      (node (ref "U18") (pin "4") (pinfunction "Trim_4") (pintype "passive"))
    )
    (net (code "31") (name "Net-(U19-A0)") (class "Default")
      (node (ref "R79") (pin "1") (pinfunction "1_1") (pintype "passive"))
      (node (ref "U19") (pin "2") (pinfunction "A0_2") (pintype "input"))
    )
    (net (code "32") (name "Net-(U19-A1)") (class "Default")
      (node (ref "R80") (pin "1") (pinfunction "1_1") (pintype "passive"))
      (node (ref "U19") (pin "1") (pinfunction "A1_1") (pintype "input"))
    )
    (net (code "33") (name "Net-(U24-EN)") (class "Default")
      (node (ref "R69") (pin "2") (pinfunction "2_2") (pintype "passive"))
      (node (ref "U24") (pin "8") (pinfunction "EN_8") (pintype "input"))
    )
    (net (code "34") (name "Net-(U24-PGOOD)") (class "Default")
      (node (ref "R70") (pin "1") (pinfunction "1_1") (pintype "passive"))
      (node (ref "U24") (pin "9") (pinfunction "PGOOD_9") (pintype "output"))
    )
    (net (code "35") (name "P3V3_MUN_FB") (class "Default")
      (node (ref "R67") (pin "1") (pinfunction "1_1") (pintype "passive"))
      (node (ref "U24") (pin "16") (pinfunction "FB_16") (pintype "input"))
    )
    (net (code "36") (name "P3V3_MUN_PHASE") (class "Default")
      (node (ref "U24") (pin "2") (pinfunction "PHASE_2") (pintype "output"))
      (node (ref "U24") (pin "22") (pinfunction "PHASE_TPD_22") (pintype "output"))
      (node (ref "U24") (pin "3") (pinfunction "PHASE_3") (pintype "output"))
      (node (ref "U24") (pin "4") (pinfunction "PHASE_4") (pintype "output"))
    )
    (net (code "37") (name "P3V3_MUN_VCC") (class "Default")
      (node (ref "C5") (pin "1") (pinfunction "1_1") (pintype "passive"))
      (node (ref "U24") (pin "17") (pinfunction "VCC_17") (pintype "power_in"))
    )
    (net (code "38") (name "P3V3_SENSE") (class "Default")
      (node (ref "R68") (pin "2") (pinfunction "2_2") (pintype "passive"))
      (node (ref "R72") (pin "1") (pinfunction "1_1") (pintype "passive"))
      (node (ref "U18") (pin "5") (pinfunction "Sense_5") (pintype "passive"))
      (node (ref "U18") (pin "6") (pinfunction "Vout_6") (pintype "power_in"))
      (node (ref "U18") (pin "7") (pinfunction "Vout_7") (pintype "power_in"))
      (node (ref "U19") (pin "8") (pinfunction "VIN+_8") (pintype "input"))
      (node (ref "U24") (pin "10") (pinfunction "VOUT_10") (pintype "output"))
      (node (ref "U24") (pin "11") (pinfunction "VOUT_11") (pintype "output"))
      (node (ref "U24") (pin "12") (pinfunction "VOUT_12") (pintype "output"))
      (node (ref "U24") (pin "13") (pinfunction "VOUT_13") (pintype "output"))
      (node (ref "U24") (pin "14") (pinfunction "VOUT_14") (pintype "output"))
      (node (ref "U24") (pin "24") (pinfunction "VOUT_TPD_24") (pintype "output"))
    )
    (net (code "39") (name "P5V_MUN_VCC") (class "Default")
      (node (ref "C3") (pin "1") (pinfunction "1_1") (pintype "passive"))
      (node (ref "U1") (pin "17") (pinfunction "VCC_17") (pintype "power_in"))
    )
    (net (code "40") (name "P5V_SENSE") (class "Default")
      (node (ref "R3") (pin "2") (pinfunction "2_2") (pintype "passive"))
      (node (ref "R8") (pin "1") (pinfunction "1_1") (pintype "passive"))
      (node (ref "U1") (pin "10") (pinfunction "VOUT_10") (pintype "output"))
      (node (ref "U1") (pin "11") (pinfunction "VOUT_11") (pintype "output"))
      (node (ref "U1") (pin "12") (pinfunction "VOUT_12") (pintype "output"))
      (node (ref "U1") (pin "13") (pinfunction "VOUT_13") (pintype "output"))
      (node (ref "U1") (pin "14") (pinfunction "VOUT_14") (pintype "output"))
      (node (ref "U1") (pin "24") (pinfunction "VOUT_TPD_24") (pintype "output"))
      (node (ref "U17") (pin "8") (pinfunction "VIN+_8") (pintype "input"))
      (node (ref "U5") (pin "5") (pinfunction "Sense_5") (pintype "passive"))
      (node (ref "U5") (pin "6") (pinfunction "Vout_6") (pintype "power_in"))
      (node (ref "U5") (pin "7") (pinfunction "Vout_7") (pintype "power_in"))
    )
    (net (code "41") (name "SENS1_I2C_SCL") (class "Default")
      (node (ref "R188") (pin "1") (pinfunction "1_1") (pintype "passive"))
      (node (ref "U17") (pin "4") (pinfunction "SCL_4") (pintype "bidirectional"))
    )
    (net (code "42") (name "SENS1_I2C_SDA") (class "Default")
      (node (ref "R187") (pin "1") (pinfunction "1_1") (pintype "passive"))
      (node (ref "U17") (pin "3") (pinfunction "SDA_3") (pintype "bidirectional"))
    )
    (net (code "43") (name "SENS_I2C_SCL") (class "Default")
      (node (ref "U19") (pin "4") (pinfunction "SCL_4") (pintype "bidirectional"))
      (node (ref "U2") (pin "4") (pinfunction "SCL_4") (pintype "bidirectional"))
    )
    (net (code "44") (name "SENS_I2C_SDA") (class "Default")
      (node (ref "U19") (pin "3") (pinfunction "SDA_3") (pintype "bidirectional"))
      (node (ref "U2") (pin "3") (pinfunction "SDA_3") (pintype "bidirectional"))
    )
    (net (code "45") (name "unconnected-(U1-BST-Pad18)") (class "Default")
      (node (ref "U1") (pin "18") (pinfunction "BST_18") (pintype "power_in"))
    )
    (net (code "46") (name "unconnected-(U24-BST-Pad18)") (class "Default")
      (node (ref "U24") (pin "18") (pinfunction "BST_18") (pintype "power_in"))
    )
  )
)
